# Teensy.net
KiCad netlist of a schematic drawn in EAGLE
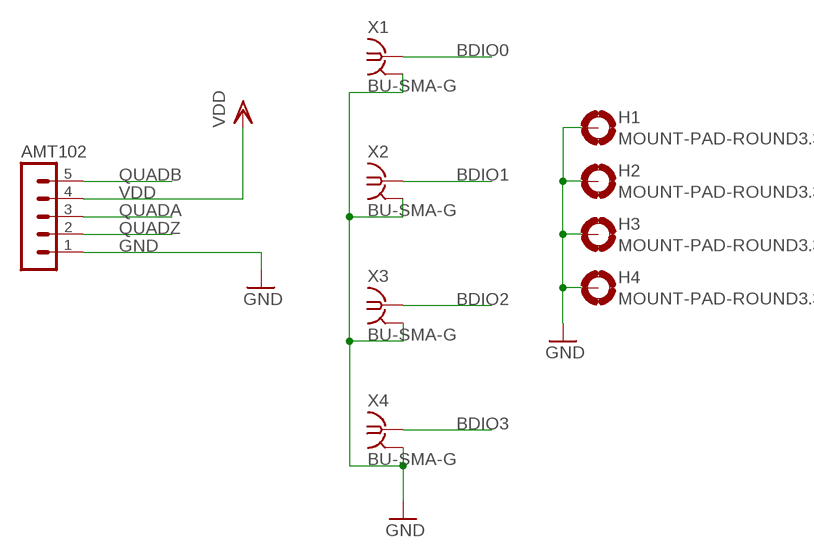
[diagram p0: schematic, sheet 1]
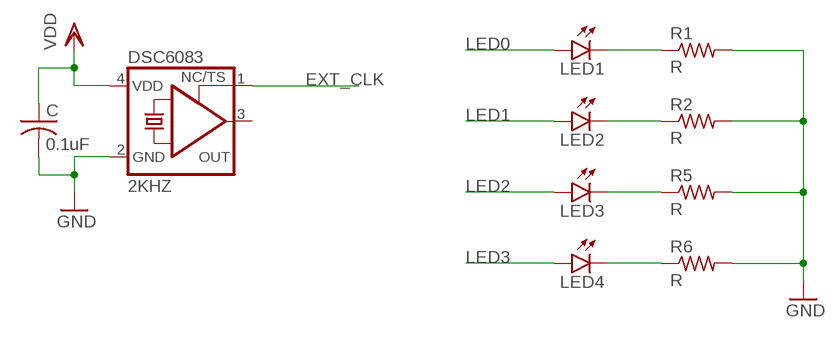
[diagram p1: schematic, sheet 2]
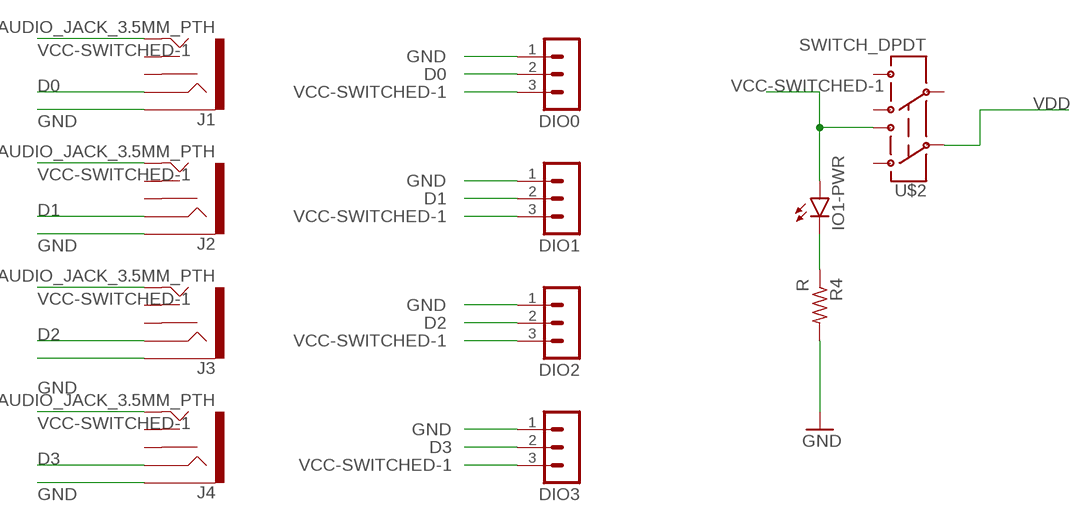
[diagram p2: schematic, sheet 3]
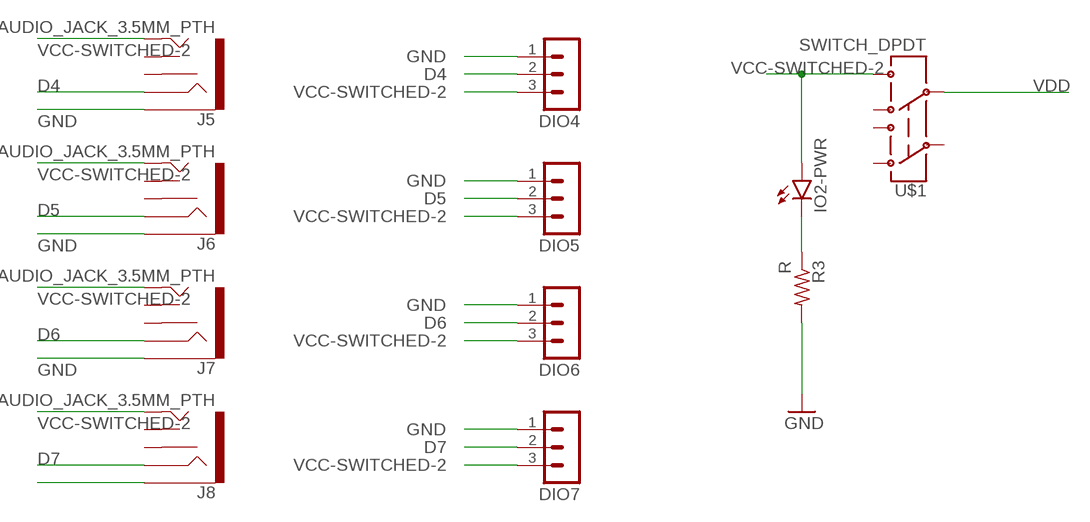
[diagram p3: schematic, sheet 4]
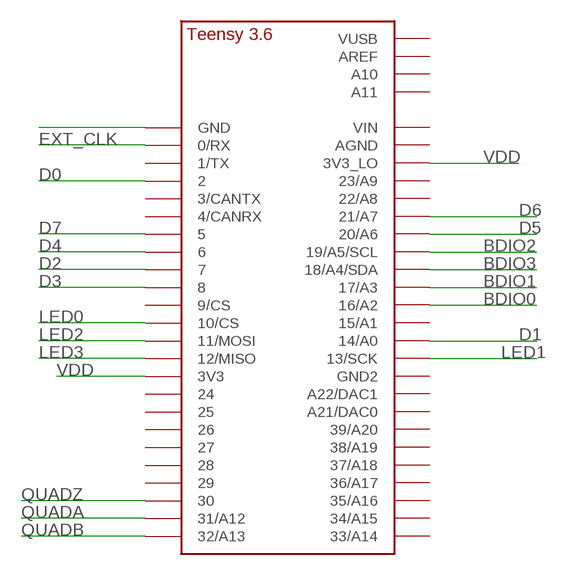
[diagram p4: schematic, sheet 5]

(export (version "E")
  (design (tool "Eeschema 10.0.6"))
  (components
    (comp (ref "DIO4")
      (value "MA03-1")
      (footprint "eagle-import:MA03-1")
      (libsource (lib "eagle-import") (part "MA03-1"))
    )
    (comp (ref "DIO5")
      (value "MA03-1")
      (footprint "eagle-import:MA03-1")
      (libsource (lib "eagle-import") (part "MA03-1"))
    )
    (comp (ref "DIO6")
      (value "MA03-1")
      (footprint "eagle-import:MA03-1")
      (libsource (lib "eagle-import") (part "MA03-1"))
    )
    (comp (ref "DIO7")
      (value "MA03-1")
      (footprint "eagle-import:MA03-1")
      (libsource (lib "eagle-import") (part "MA03-1"))
    )
    (comp (ref "IO2-PWR")
      (value "LEDCHIP-LED0603")
      (footprint "eagle-import:CHIP-LED0603")
      (libsource (lib "eagle-import") (part "LEDCHIP-LED0603"))
    )
    (comp (ref "J5")
      (value "AUDIO_JACK_3.5MM_PTH")
      (footprint "eagle-import:AUDIO-JACK")
      (libsource (lib "eagle-import") (part "AUDIO_JACK_3.5MM_PTH"))
    )
    (comp (ref "J6")
      (value "AUDIO_JACK_3.5MM_PTH")
      (footprint "eagle-import:AUDIO-JACK")
      (libsource (lib "eagle-import") (part "AUDIO_JACK_3.5MM_PTH"))
    )
    (comp (ref "J7")
      (value "AUDIO_JACK_3.5MM_PTH")
      (footprint "eagle-import:AUDIO-JACK")
      (libsource (lib "eagle-import") (part "AUDIO_JACK_3.5MM_PTH"))
    )
    (comp (ref "J8")
      (value "AUDIO_JACK_3.5MM_PTH")
      (footprint "eagle-import:AUDIO-JACK")
      (libsource (lib "eagle-import") (part "AUDIO_JACK_3.5MM_PTH"))
    )
    (comp (ref "R3")
      (value "R")
      (footprint "eagle-import:R0603")
      (libsource (lib "eagle-import") (part "R-US_R0603"))
    )
    (comp (ref "U$1")
      (value "SWITCH_DPDT")
      (footprint "eagle-import:JS_DPDT_TH")
      (libsource (lib "eagle-import") (part "SWITCH_DPDT"))
    )
    (comp (ref "DIO0")
      (value "MA03-1")
      (footprint "eagle-import:MA03-1")
      (libsource (lib "eagle-import") (part "MA03-1"))
    )
    (comp (ref "DIO1")
      (value "MA03-1")
      (footprint "eagle-import:MA03-1")
      (libsource (lib "eagle-import") (part "MA03-1"))
    )
    (comp (ref "DIO2")
      (value "MA03-1")
      (footprint "eagle-import:MA03-1")
      (libsource (lib "eagle-import") (part "MA03-1"))
    )
    (comp (ref "DIO3")
      (value "MA03-1")
      (footprint "eagle-import:MA03-1")
      (libsource (lib "eagle-import") (part "MA03-1"))
    )
    (comp (ref "IO1-PWR")
      (value "LEDCHIP-LED0603")
      (footprint "eagle-import:CHIP-LED0603")
      (libsource (lib "eagle-import") (part "LEDCHIP-LED0603"))
    )
    (comp (ref "J1")
      (value "AUDIO_JACK_3.5MM_PTH")
      (footprint "eagle-import:AUDIO-JACK")
      (libsource (lib "eagle-import") (part "AUDIO_JACK_3.5MM_PTH"))
    )
    (comp (ref "J2")
      (value "AUDIO_JACK_3.5MM_PTH")
      (footprint "eagle-import:AUDIO-JACK")
      (libsource (lib "eagle-import") (part "AUDIO_JACK_3.5MM_PTH"))
    )
    (comp (ref "J3")
      (value "AUDIO_JACK_3.5MM_PTH")
      (footprint "eagle-import:AUDIO-JACK")
      (libsource (lib "eagle-import") (part "AUDIO_JACK_3.5MM_PTH"))
    )
    (comp (ref "J4")
      (value "AUDIO_JACK_3.5MM_PTH")
      (footprint "eagle-import:AUDIO-JACK")
      (libsource (lib "eagle-import") (part "AUDIO_JACK_3.5MM_PTH"))
    )
    (comp (ref "R4")
      (value "R")
      (footprint "eagle-import:R0603")
      (libsource (lib "eagle-import") (part "R-US_R0603"))
    )
    (comp (ref "U$2")
      (value "SWITCH_DPDT")
      (footprint "eagle-import:JS_DPDT_TH")
      (libsource (lib "eagle-import") (part "SWITCH_DPDT"))
    )
    (comp (ref "U$3")
      (value "TEENSY_3.5/3.6_BASIC")
      (footprint "eagle-import:TEENSY_3.5_3.6_BASIC")
      (libsource (lib "eagle-import") (part "TEENSY_3.5/3.6_BASIC"))
    )
    (comp (ref "C")
      (value "0.1uF")
      (footprint "eagle-import:C0603")
      (libsource (lib "eagle-import") (part "C-USC0603"))
    )
    (comp (ref "DSC6083")
      (value "2KHZ")
      (footprint "eagle-import:3.2X2.5_KXO-V96")
      (libsource (lib "eagle-import") (part "KXO-PXO/XO-V96"))
    )
    (comp (ref "LED1")
      (value "LEDCHIPLED_0603")
      (footprint "eagle-import:CHIPLED_0603")
      (libsource (lib "eagle-import") (part "LEDCHIPLED_0603"))
    )
    (comp (ref "LED2")
      (value "LEDCHIP-LED0603")
      (footprint "eagle-import:CHIP-LED0603")
      (libsource (lib "eagle-import") (part "LEDCHIP-LED0603"))
    )
    (comp (ref "LED3")
      (value "LEDCHIP-LED0603")
      (footprint "eagle-import:CHIP-LED0603")
      (libsource (lib "eagle-import") (part "LEDCHIP-LED0603"))
    )
    (comp (ref "LED4")
      (value "LEDCHIP-LED0603")
      (footprint "eagle-import:CHIP-LED0603")
      (libsource (lib "eagle-import") (part "LEDCHIP-LED0603"))
    )
    (comp (ref "R1")
      (value "R")
      (footprint "eagle-import:R0603")
      (libsource (lib "eagle-import") (part "R-US_R0603"))
    )
    (comp (ref "R2")
      (value "R")
      (footprint "eagle-import:R0603")
      (libsource (lib "eagle-import") (part "R-US_R0603"))
    )
    (comp (ref "R5")
      (value "R")
      (footprint "eagle-import:R0603")
      (libsource (lib "eagle-import") (part "R-US_R0603"))
    )
    (comp (ref "R6")
      (value "R")
      (footprint "eagle-import:R0603")
      (libsource (lib "eagle-import") (part "R-US_R0603"))
    )
    (comp (ref "AMT102")
      (value "MA05-1")
      (footprint "eagle-import:MA05-1")
      (libsource (lib "eagle-import") (part "MA05-1"))
    )
    (comp (ref "H1")
      (value "MOUNT-PAD-ROUND3.3")
      (footprint "eagle-import:3,3-PAD")
      (libsource (lib "eagle-import") (part "MOUNT-PAD-ROUND3.3"))
    )
    (comp (ref "H2")
      (value "MOUNT-PAD-ROUND3.3")
      (footprint "eagle-import:3,3-PAD")
      (libsource (lib "eagle-import") (part "MOUNT-PAD-ROUND3.3"))
    )
    (comp (ref "H3")
      (value "MOUNT-PAD-ROUND3.3")
      (footprint "eagle-import:3,3-PAD")
      (libsource (lib "eagle-import") (part "MOUNT-PAD-ROUND3.3"))
    )
    (comp (ref "H4")
      (value "MOUNT-PAD-ROUND3.3")
      (footprint "eagle-import:3,3-PAD")
      (libsource (lib "eagle-import") (part "MOUNT-PAD-ROUND3.3"))
    )
    (comp (ref "X1")
      (value "BU-SMA-G")
      (footprint "eagle-import:BU-SMA-G")
      (libsource (lib "eagle-import") (part "BU-SMA-G"))
    )
    (comp (ref "X2")
      (value "BU-SMA-G")
      (footprint "eagle-import:BU-SMA-G")
      (libsource (lib "eagle-import") (part "BU-SMA-G"))
    )
    (comp (ref "X3")
      (value "BU-SMA-G")
      (footprint "eagle-import:BU-SMA-G")
      (libsource (lib "eagle-import") (part "BU-SMA-G"))
    )
    (comp (ref "X4")
      (value "BU-SMA-G")
      (footprint "eagle-import:BU-SMA-G")
      (libsource (lib "eagle-import") (part "BU-SMA-G"))
    )
  )
  (nets
    (net (code "1") (name "BDIO0") (class "Default")
      (node (ref "U$3") (pin "16/A2") (pinfunction "16/A2_16/A2") (pintype "bidirectional"))
      (node (ref "X1") (pin "1") (pinfunction "1_1") (pintype "passive"))
    )
    (net (code "2") (name "BDIO1") (class "Default")
      (node (ref "U$3") (pin "17/A3") (pinfunction "17/A3_17/A3") (pintype "bidirectional"))
      (node (ref "X2") (pin "1") (pinfunction "1_1") (pintype "passive"))
    )
    (net (code "3") (name "BDIO2") (class "Default")
      (node (ref "U$3") (pin "19/A5/SCL") (pinfunction "19/A5/SCL_19/A5/SCL") (pintype "bidirectional"))
      (node (ref "X3") (pin "1") (pinfunction "1_1") (pintype "passive"))
    )
    (net (code "4") (name "BDIO3") (class "Default")
      (node (ref "U$3") (pin "18/A4/SDA") (pinfunction "18/A4/SDA_18/A4/SDA") (pintype "bidirectional"))
      (node (ref "X4") (pin "1") (pinfunction "1_1") (pintype "passive"))
    )
    (net (code "5") (name "D0") (class "Default")
      (node (ref "DIO0") (pin "2") (pinfunction "2_2") (pintype "passive"))
      (node (ref "J1") (pin "RING") (pinfunction "RING_RING") (pintype "bidirectional"))
      (node (ref "U$3") (pin "2") (pinfunction "2_2") (pintype "bidirectional"))
    )
    (net (code "6") (name "D1") (class "Default")
      (node (ref "DIO1") (pin "2") (pinfunction "2_2") (pintype "passive"))
      (node (ref "J2") (pin "RING") (pinfunction "RING_RING") (pintype "bidirectional"))
      (node (ref "U$3") (pin "14/A0") (pinfunction "14/A0_14/A0") (pintype "bidirectional"))
    )
    (net (code "7") (name "D2") (class "Default")
      (node (ref "DIO2") (pin "2") (pinfunction "2_2") (pintype "passive"))
      (node (ref "J3") (pin "RING") (pinfunction "RING_RING") (pintype "bidirectional"))
      (node (ref "U$3") (pin "7") (pinfunction "7_7") (pintype "bidirectional"))
    )
    (net (code "8") (name "D3") (class "Default")
      (node (ref "DIO3") (pin "2") (pinfunction "2_2") (pintype "passive"))
      (node (ref "J4") (pin "RING") (pinfunction "RING_RING") (pintype "bidirectional"))
      (node (ref "U$3") (pin "8") (pinfunction "8_8") (pintype "bidirectional"))
    )
    (net (code "9") (name "D4") (class "Default")
      (node (ref "DIO4") (pin "2") (pinfunction "2_2") (pintype "passive"))
      (node (ref "J5") (pin "RING") (pinfunction "RING_RING") (pintype "bidirectional"))
      (node (ref "U$3") (pin "6") (pinfunction "6_6") (pintype "bidirectional"))
    )
    (net (code "10") (name "D5") (class "Default")
      (node (ref "DIO5") (pin "2") (pinfunction "2_2") (pintype "passive"))
      (node (ref "J6") (pin "RING") (pinfunction "RING_RING") (pintype "bidirectional"))
      (node (ref "U$3") (pin "20/A6") (pinfunction "20/A6_20/A6") (pintype "bidirectional"))
    )
    (net (code "11") (name "D6") (class "Default")
      (node (ref "DIO6") (pin "2") (pinfunction "2_2") (pintype "passive"))
      (node (ref "J7") (pin "RING") (pinfunction "RING_RING") (pintype "bidirectional"))
      (node (ref "U$3") (pin "21/A7") (pinfunction "21/A7_21/A7") (pintype "bidirectional"))
    )
    (net (code "12") (name "D7") (class "Default")
      (node (ref "DIO7") (pin "2") (pinfunction "2_2") (pintype "passive"))
      (node (ref "J8") (pin "RING") (pinfunction "RING_RING") (pintype "bidirectional"))
      (node (ref "U$3") (pin "5") (pinfunction "5_5") (pintype "bidirectional"))
    )
    (net (code "13") (name "EXT_CLK") (class "Default")
      (node (ref "DSC6083") (pin "1") (pinfunction "TS_1") (pintype "passive"))
      (node (ref "U$3") (pin "0/RX") (pinfunction "0/RX_0/RX") (pintype "bidirectional"))
    )
    (net (code "14") (name "GND") (class "Default")
      (node (ref "AMT102") (pin "1") (pinfunction "1_1") (pintype "passive"))
      (node (ref "C") (pin "2") (pinfunction "2_2") (pintype "passive"))
      (node (ref "DIO0") (pin "1") (pinfunction "1_1") (pintype "passive"))
      (node (ref "DIO1") (pin "1") (pinfunction "1_1") (pintype "passive"))
      (node (ref "DIO2") (pin "1") (pinfunction "1_1") (pintype "passive"))
      (node (ref "DIO3") (pin "1") (pinfunction "1_1") (pintype "passive"))
      (node (ref "DIO4") (pin "1") (pinfunction "1_1") (pintype "passive"))
      (node (ref "DIO5") (pin "1") (pinfunction "1_1") (pintype "passive"))
      (node (ref "DIO6") (pin "1") (pinfunction "1_1") (pintype "passive"))
      (node (ref "DIO7") (pin "1") (pinfunction "1_1") (pintype "passive"))
      (node (ref "DSC6083") (pin "2") (pinfunction "GND_2") (pintype "power_in"))
      (node (ref "H1") (pin "B3,3") (pinfunction "MOUNT_B3,3") (pintype "passive"))
      (node (ref "H2") (pin "B3,3") (pinfunction "MOUNT_B3,3") (pintype "passive"))
      (node (ref "H3") (pin "B3,3") (pinfunction "MOUNT_B3,3") (pintype "passive"))
      (node (ref "H4") (pin "B3,3") (pinfunction "MOUNT_B3,3") (pintype "passive"))
      (node (ref "J1") (pin "SLEEVE") (pinfunction "SLEEVE_SLEEVE") (pintype "bidirectional"))
      (node (ref "J2") (pin "SLEEVE") (pinfunction "SLEEVE_SLEEVE") (pintype "bidirectional"))
      (node (ref "J3") (pin "SLEEVE") (pinfunction "SLEEVE_SLEEVE") (pintype "bidirectional"))
      (node (ref "J4") (pin "SLEEVE") (pinfunction "SLEEVE_SLEEVE") (pintype "bidirectional"))
      (node (ref "J5") (pin "SLEEVE") (pinfunction "SLEEVE_SLEEVE") (pintype "bidirectional"))
      (node (ref "J6") (pin "SLEEVE") (pinfunction "SLEEVE_SLEEVE") (pintype "bidirectional"))
      (node (ref "J7") (pin "SLEEVE") (pinfunction "SLEEVE_SLEEVE") (pintype "bidirectional"))
      (node (ref "J8") (pin "SLEEVE") (pinfunction "SLEEVE_SLEEVE") (pintype "bidirectional"))
      (node (ref "R1") (pin "2") (pinfunction "2_2") (pintype "passive"))
      (node (ref "R2") (pin "2") (pinfunction "2_2") (pintype "passive"))
      (node (ref "R3") (pin "2") (pinfunction "2_2") (pintype "passive"))
      (node (ref "R4") (pin "2") (pinfunction "2_2") (pintype "passive"))
      (node (ref "R5") (pin "2") (pinfunction "2_2") (pintype "passive"))
      (node (ref "R6") (pin "2") (pinfunction "2_2") (pintype "passive"))
      (node (ref "U$3") (pin "GND") (pinfunction "GND_GND") (pintype "bidirectional"))
      (node (ref "X1") (pin "2") (pinfunction "2_2") (pintype "passive"))
      (node (ref "X1") (pin "3") (pinfunction "2_3") (pintype "passive"))
      (node (ref "X1") (pin "4") (pinfunction "2_4") (pintype "passive"))
      (node (ref "X1") (pin "5") (pinfunction "2_5") (pintype "passive"))
      (node (ref "X2") (pin "2") (pinfunction "2_2") (pintype "passive"))
      (node (ref "X2") (pin "3") (pinfunction "2_3") (pintype "passive"))
      (node (ref "X2") (pin "4") (pinfunction "2_4") (pintype "passive"))
      (node (ref "X2") (pin "5") (pinfunction "2_5") (pintype "passive"))
      (node (ref "X3") (pin "2") (pinfunction "2_2") (pintype "passive"))
      (node (ref "X3") (pin "3") (pinfunction "2_3") (pintype "passive"))
      (node (ref "X3") (pin "4") (pinfunction "2_4") (pintype "passive"))
      (node (ref "X3") (pin "5") (pinfunction "2_5") (pintype "passive"))
      (node (ref "X4") (pin "2") (pinfunction "2_2") (pintype "passive"))
      (node (ref "X4") (pin "3") (pinfunction "2_3") (pintype "passive"))
      (node (ref "X4") (pin "4") (pinfunction "2_4") (pintype "passive"))
      (node (ref "X4") (pin "5") (pinfunction "2_5") (pintype "passive"))
    )
    (net (code "15") (name "LED0") (class "Default")
      (node (ref "LED1") (pin "A") (pinfunction "A_A") (pintype "passive"))
      (node (ref "U$3") (pin "10/CS") (pinfunction "10/CS_10/CS") (pintype "bidirectional"))
    )
    (net (code "16") (name "LED1") (class "Default")
      (node (ref "LED2") (pin "A") (pinfunction "A_A") (pintype "passive"))
      (node (ref "U$3") (pin "13/SCK") (pinfunction "13/SCK_13/SCK") (pintype "bidirectional"))
    )
    (net (code "17") (name "LED2") (class "Default")
      (node (ref "LED3") (pin "A") (pinfunction "A_A") (pintype "passive"))
      (node (ref "U$3") (pin "11/MOSI") (pinfunction "11/MOSI_11/MOSI") (pintype "bidirectional"))
    )
    (net (code "18") (name "LED3") (class "Default")
      (node (ref "LED4") (pin "A") (pinfunction "A_A") (pintype "passive"))
      (node (ref "U$3") (pin "12/MISO") (pinfunction "12/MISO_12/MISO") (pintype "bidirectional"))
    )
    (net (code "19") (name "Net-(IO1-PWR-PadC)") (class "Default")
      (node (ref "IO1-PWR") (pin "C") (pinfunction "C_C") (pintype "passive"))
      (node (ref "R4") (pin "1") (pinfunction "1_1") (pintype "passive"))
    )
    (net (code "20") (name "Net-(IO2-PWR-PadC)") (class "Default")
      (node (ref "IO2-PWR") (pin "C") (pinfunction "C_C") (pintype "passive"))
      (node (ref "R3") (pin "1") (pinfunction "1_1") (pintype "passive"))
    )
    (net (code "21") (name "Net-(LED1-PadC)") (class "Default")
      (node (ref "LED1") (pin "C") (pinfunction "C_C") (pintype "passive"))
      (node (ref "R1") (pin "1") (pinfunction "1_1") (pintype "passive"))
    )
    (net (code "22") (name "Net-(LED2-PadC)") (class "Default")
      (node (ref "LED2") (pin "C") (pinfunction "C_C") (pintype "passive"))
      (node (ref "R2") (pin "1") (pinfunction "1_1") (pintype "passive"))
    )
    (net (code "23") (name "Net-(LED3-PadC)") (class "Default")
      (node (ref "LED3") (pin "C") (pinfunction "C_C") (pintype "passive"))
      (node (ref "R5") (pin "1") (pinfunction "1_1") (pintype "passive"))
    )
    (net (code "24") (name "Net-(LED4-PadC)") (class "Default")
      (node (ref "LED4") (pin "C") (pinfunction "C_C") (pintype "passive"))
      (node (ref "R6") (pin "1") (pinfunction "1_1") (pintype "passive"))
    )
    (net (code "25") (name "QUADA") (class "Default")
      (node (ref "AMT102") (pin "3") (pinfunction "3_3") (pintype "passive"))
      (node (ref "U$3") (pin "31/A12") (pinfunction "31/A12_31/A12") (pintype "bidirectional"))
    )
    (net (code "26") (name "QUADB") (class "Default")
      (node (ref "AMT102") (pin "5") (pinfunction "5_5") (pintype "passive"))
      (node (ref "U$3") (pin "32/A13") (pinfunction "32/A13_32/A13") (pintype "bidirectional"))
    )
    (net (code "27") (name "QUADZ") (class "Default")
      (node (ref "AMT102") (pin "2") (pinfunction "2_2") (pintype "passive"))
      (node (ref "U$3") (pin "30") (pinfunction "30_30") (pintype "bidirectional"))
    )
    (net (code "28") (name "VCC-SWITCHED-1") (class "Default")
      (node (ref "DIO0") (pin "3") (pinfunction "3_3") (pintype "passive"))
      (node (ref "DIO1") (pin "3") (pinfunction "3_3") (pintype "passive"))
      (node (ref "DIO2") (pin "3") (pinfunction "3_3") (pintype "passive"))
      (node (ref "DIO3") (pin "3") (pinfunction "3_3") (pintype "passive"))
      (node (ref "IO1-PWR") (pin "A") (pinfunction "A_A") (pintype "passive"))
      (node (ref "J1") (pin "TIP") (pinfunction "TIP_TIP") (pintype "bidirectional"))
      (node (ref "J2") (pin "TIP") (pinfunction "TIP_TIP") (pintype "bidirectional"))
      (node (ref "J3") (pin "TIP") (pinfunction "TIP_TIP") (pintype "bidirectional"))
      (node (ref "J4") (pin "TIP") (pinfunction "TIP_TIP") (pintype "bidirectional"))
      (node (ref "U$2") (pin "3") (pinfunction "3_3") (pintype "bidirectional"))
    )
    (net (code "29") (name "VCC-SWITCHED-2") (class "Default")
      (node (ref "DIO4") (pin "3") (pinfunction "3_3") (pintype "passive"))
      (node (ref "DIO5") (pin "3") (pinfunction "3_3") (pintype "passive"))
      (node (ref "DIO6") (pin "3") (pinfunction "3_3") (pintype "passive"))
      (node (ref "DIO7") (pin "3") (pinfunction "3_3") (pintype "passive"))
      (node (ref "IO2-PWR") (pin "A") (pinfunction "A_A") (pintype "passive"))
      (node (ref "J5") (pin "TIP") (pinfunction "TIP_TIP") (pintype "bidirectional"))
      (node (ref "J6") (pin "TIP") (pinfunction "TIP_TIP") (pintype "bidirectional"))
      (node (ref "J7") (pin "TIP") (pinfunction "TIP_TIP") (pintype "bidirectional"))
      (node (ref "J8") (pin "TIP") (pinfunction "TIP_TIP") (pintype "bidirectional"))
      (node (ref "U$1") (pin "6") (pinfunction "6_6") (pintype "bidirectional"))
    )
    (net (code "30") (name "VDD") (class "Default")
      (node (ref "AMT102") (pin "4") (pinfunction "4_4") (pintype "passive"))
      (node (ref "C") (pin "1") (pinfunction "1_1") (pintype "passive"))
      (node (ref "DSC6083") (pin "4") (pinfunction "VDD_4") (pintype "power_in"))
      (node (ref "U$1") (pin "5") (pinfunction "5_5") (pintype "bidirectional"))
      (node (ref "U$2") (pin "2") (pinfunction "2_2") (pintype "bidirectional"))
      (node (ref "U$3") (pin "3V3") (pinfunction "3V3_3V3") (pintype "bidirectional"))
      (node (ref "U$3") (pin "3V3_LO") (pinfunction "3V3_LO_3V3_LO") (pintype "bidirectional"))
    )
    (net (code "31") (name "unconnected-(DSC6083-OUT-Pad3)") (class "Default")
      (node (ref "DSC6083") (pin "3") (pinfunction "OUT_3") (pintype "output"))
    )
    (net (code "32") (name "unconnected-(J1-PadRSH)") (class "Default")
      (node (ref "J1") (pin "RSH") (pinfunction "RSH_RSH") (pintype "bidirectional"))
    )
    (net (code "33") (name "unconnected-(J1-PadTSH)") (class "Default")
      (node (ref "J1") (pin "TSH") (pinfunction "TSH_TSH") (pintype "bidirectional"))
    )
    (net (code "34") (name "unconnected-(J2-PadRSH)") (class "Default")
      (node (ref "J2") (pin "RSH") (pinfunction "RSH_RSH") (pintype "bidirectional"))
    )
    (net (code "35") (name "unconnected-(J2-PadTSH)") (class "Default")
      (node (ref "J2") (pin "TSH") (pinfunction "TSH_TSH") (pintype "bidirectional"))
    )
    (net (code "36") (name "unconnected-(J3-PadRSH)") (class "Default")
      (node (ref "J3") (pin "RSH") (pinfunction "RSH_RSH") (pintype "bidirectional"))
    )
    (net (code "37") (name "unconnected-(J3-PadTSH)") (class "Default")
      (node (ref "J3") (pin "TSH") (pinfunction "TSH_TSH") (pintype "bidirectional"))
    )
    (net (code "38") (name "unconnected-(J4-PadRSH)") (class "Default")
      (node (ref "J4") (pin "RSH") (pinfunction "RSH_RSH") (pintype "bidirectional"))
    )
    (net (code "39") (name "unconnected-(J4-PadTSH)") (class "Default")
      (node (ref "J4") (pin "TSH") (pinfunction "TSH_TSH") (pintype "bidirectional"))
    )
    (net (code "40") (name "unconnected-(J5-PadRSH)") (class "Default")
      (node (ref "J5") (pin "RSH") (pinfunction "RSH_RSH") (pintype "bidirectional"))
    )
    (net (code "41") (name "unconnected-(J5-PadTSH)") (class "Default")
      (node (ref "J5") (pin "TSH") (pinfunction "TSH_TSH") (pintype "bidirectional"))
    )
    (net (code "42") (name "unconnected-(J6-PadRSH)") (class "Default")
      (node (ref "J6") (pin "RSH") (pinfunction "RSH_RSH") (pintype "bidirectional"))
    )
    (net (code "43") (name "unconnected-(J6-PadTSH)") (class "Default")
      (node (ref "J6") (pin "TSH") (pinfunction "TSH_TSH") (pintype "bidirectional"))
    )
    (net (code "44") (name "unconnected-(J7-PadRSH)") (class "Default")
      (node (ref "J7") (pin "RSH") (pinfunction "RSH_RSH") (pintype "bidirectional"))
    )
    (net (code "45") (name "unconnected-(J7-PadTSH)") (class "Default")
      (node (ref "J7") (pin "TSH") (pinfunction "TSH_TSH") (pintype "bidirectional"))
    )
    (net (code "46") (name "unconnected-(J8-PadRSH)") (class "Default")
      (node (ref "J8") (pin "RSH") (pinfunction "RSH_RSH") (pintype "bidirectional"))
    )
    (net (code "47") (name "unconnected-(J8-PadTSH)") (class "Default")
      (node (ref "J8") (pin "TSH") (pinfunction "TSH_TSH") (pintype "bidirectional"))
    )
    (net (code "48") (name "unconnected-(U$1-Pad1)") (class "Default")
      (node (ref "U$1") (pin "1") (pinfunction "1_1") (pintype "bidirectional"))
    )
    (net (code "49") (name "unconnected-(U$1-Pad2)") (class "Default")
      (node (ref "U$1") (pin "2") (pinfunction "2_2") (pintype "bidirectional"))
    )
    (net (code "50") (name "unconnected-(U$1-Pad3)") (class "Default")
      (node (ref "U$1") (pin "3") (pinfunction "3_3") (pintype "bidirectional"))
    )
    (net (code "51") (name "unconnected-(U$1-Pad4)") (class "Default")
      (node (ref "U$1") (pin "4") (pinfunction "4_4") (pintype "bidirectional"))
    )
    (net (code "52") (name "unconnected-(U$2-Pad1)") (class "Default")
      (node (ref "U$2") (pin "1") (pinfunction "1_1") (pintype "bidirectional"))
    )
    (net (code "53") (name "unconnected-(U$2-Pad4)") (class "Default")
      (node (ref "U$2") (pin "4") (pinfunction "4_4") (pintype "bidirectional"))
    )
    (net (code "54") (name "unconnected-(U$2-Pad5)") (class "Default")
      (node (ref "U$2") (pin "5") (pinfunction "5_5") (pintype "bidirectional"))
    )
    (net (code "55") (name "unconnected-(U$2-Pad6)") (class "Default")
      (node (ref "U$2") (pin "6") (pinfunction "6_6") (pintype "bidirectional"))
    )
    (net (code "56") (name "unconnected-(U$3-A21{slash}DAC0-Pad21{slash}DAC0)") (class "Default")
      (node (ref "U$3") (pin "21/DAC0") (pinfunction "A21/DAC0_21/DAC0") (pintype "bidirectional"))
    )
    (net (code "57") (name "unconnected-(U$3-Pad1{slash}TX)") (class "Default")
      (node (ref "U$3") (pin "1/TX") (pinfunction "1/TX_1/TX") (pintype "bidirectional"))
    )
    (net (code "58") (name "unconnected-(U$3-Pad3{slash}CANTX)") (class "Default")
      (node (ref "U$3") (pin "3/CANTX") (pinfunction "3/CANTX_3/CANTX") (pintype "bidirectional"))
    )
    (net (code "59") (name "unconnected-(U$3-Pad4{slash}CANRX)") (class "Default")
      (node (ref "U$3") (pin "4/CANRX") (pinfunction "4/CANRX_4/CANRX") (pintype "bidirectional"))
    )
    (net (code "60") (name "unconnected-(U$3-Pad9{slash}CS)") (class "Default")
      (node (ref "U$3") (pin "9/CS") (pinfunction "9/CS_9/CS") (pintype "bidirectional"))
    )
    (net (code "61") (name "unconnected-(U$3-Pad15{slash}A1)") (class "Default")
      (node (ref "U$3") (pin "15/A1") (pinfunction "15/A1_15/A1") (pintype "bidirectional"))
    )
    (net (code "62") (name "unconnected-(U$3-Pad22{slash}A8)") (class "Default")
      (node (ref "U$3") (pin "22/A8") (pinfunction "22/A8_22/A8") (pintype "bidirectional"))
    )
    (net (code "63") (name "unconnected-(U$3-Pad23{slash}A9)") (class "Default")
      (node (ref "U$3") (pin "23/A9") (pinfunction "23/A9_23/A9") (pintype "bidirectional"))
    )
    (net (code "64") (name "unconnected-(U$3-Pad24)") (class "Default")
      (node (ref "U$3") (pin "24") (pinfunction "24_24") (pintype "bidirectional"))
    )
    (net (code "65") (name "unconnected-(U$3-Pad25)") (class "Default")
      (node (ref "U$3") (pin "25") (pinfunction "25_25") (pintype "bidirectional"))
    )
    (net (code "66") (name "unconnected-(U$3-Pad26)") (class "Default")
      (node (ref "U$3") (pin "26") (pinfunction "26_26") (pintype "bidirectional"))
    )
    (net (code "67") (name "unconnected-(U$3-Pad27)") (class "Default")
      (node (ref "U$3") (pin "27") (pinfunction "27_27") (pintype "bidirectional"))
    )
    (net (code "68") (name "unconnected-(U$3-Pad28)") (class "Default")
      (node (ref "U$3") (pin "28") (pinfunction "28_28") (pintype "bidirectional"))
    )
    (net (code "69") (name "unconnected-(U$3-Pad29)") (class "Default")
      (node (ref "U$3") (pin "29") (pinfunction "29_29") (pintype "bidirectional"))
    )
    (net (code "70") (name "unconnected-(U$3-Pad33{slash}A14)") (class "Default")
      (node (ref "U$3") (pin "33/A14") (pinfunction "33/A14_33/A14") (pintype "bidirectional"))
    )
    (net (code "71") (name "unconnected-(U$3-Pad34{slash}A15)") (class "Default")
      (node (ref "U$3") (pin "34/A15") (pinfunction "34/A15_34/A15") (pintype "bidirectional"))
    )
    (net (code "72") (name "unconnected-(U$3-Pad35{slash}A16)") (class "Default")
      (node (ref "U$3") (pin "35/A16") (pinfunction "35/A16_35/A16") (pintype "bidirectional"))
    )
    (net (code "73") (name "unconnected-(U$3-Pad36{slash}A17)") (class "Default")
      (node (ref "U$3") (pin "36/A17") (pinfunction "36/A17_36/A17") (pintype "bidirectional"))
    )
    (net (code "74") (name "unconnected-(U$3-Pad37{slash}A18)") (class "Default")
      (node (ref "U$3") (pin "37/A18") (pinfunction "37/A18_37/A18") (pintype "bidirectional"))
    )
    (net (code "75") (name "unconnected-(U$3-Pad38{slash}A19)") (class "Default")
      (node (ref "U$3") (pin "38/A19") (pinfunction "38/A19_38/A19") (pintype "bidirectional"))
    )
    (net (code "76") (name "unconnected-(U$3-Pad39{slash}A20)") (class "Default")
      (node (ref "U$3") (pin "39/A20") (pinfunction "39/A20_39/A20") (pintype "bidirectional"))
    )
    (net (code "77") (name "unconnected-(U$3-PadA10)") (class "Default")
      (node (ref "U$3") (pin "A10") (pinfunction "A10_A10") (pintype "bidirectional"))
    )
    (net (code "78") (name "unconnected-(U$3-PadA11)") (class "Default")
      (node (ref "U$3") (pin "A11") (pinfunction "A11_A11") (pintype "bidirectional"))
    )
    (net (code "79") (name "unconnected-(U$3-PadA22{slash}DAC1)") (class "Default")
      (node (ref "U$3") (pin "A22/DAC1") (pinfunction "A22/DAC1_A22/DAC1") (pintype "bidirectional"))
    )
    (net (code "80") (name "unconnected-(U$3-PadAGND)") (class "Default")
      (node (ref "U$3") (pin "AGND") (pinfunction "AGND_AGND") (pintype "bidirectional"))
    )
    (net (code "81") (name "unconnected-(U$3-PadAREF)") (class "Default")
      (node (ref "U$3") (pin "AREF") (pinfunction "AREF_AREF") (pintype "bidirectional"))
    )
    (net (code "82") (name "unconnected-(U$3-PadGND2)") (class "Default")
      (node (ref "U$3") (pin "GND2") (pinfunction "GND2_GND2") (pintype "bidirectional"))
    )
    (net (code "83") (name "unconnected-(U$3-PadVIN)") (class "Default")
      (node (ref "U$3") (pin "VIN") (pinfunction "VIN_VIN") (pintype "bidirectional"))
    )
    (net (code "84") (name "unconnected-(U$3-PadVUSB)") (class "Default")
      (node (ref "U$3") (pin "VUSB") (pinfunction "VUSB_VUSB") (pintype "bidirectional"))
    )
  )
)
